# seeker_md_board.net
KiCad netlist of a schematic drawn in EAGLE
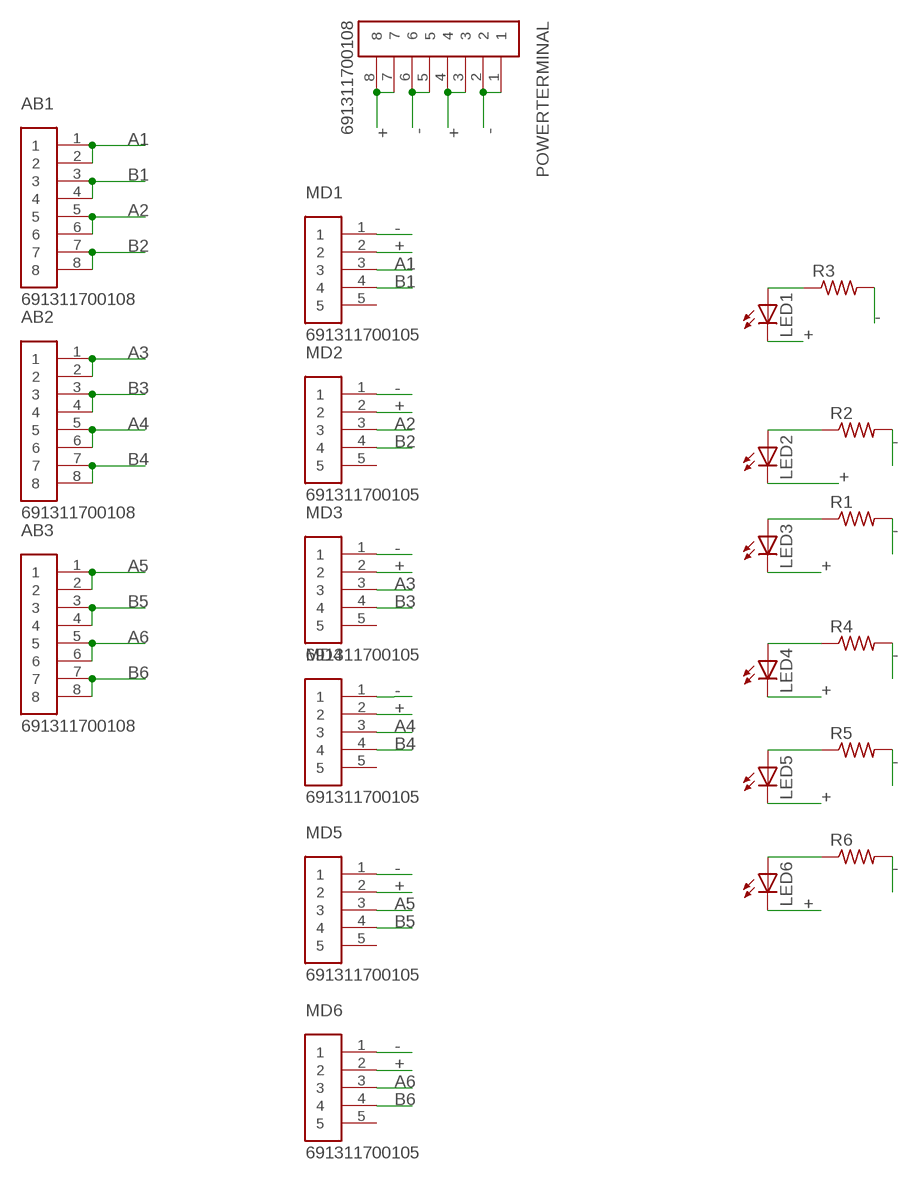
[diagram p0: schematic, sheet 1]

(export (version "E")
  (design (tool "Eeschema 10.0.6"))
  (components
    (comp (ref "AB1")
      (value "691311700108")
      (footprint "eagle-import:TERMINALBLOCK_PLUGGABLE-8-5MM")
      (fields
        (field (name "DIGIKEY_PART_NO") "732-2792-ND")
        (field (name "MANUFACTURER") "WURTH ELEKTRONIK")
        (field (name "CREATED_BY") "PCBLayout.com")
      )
      (libsource (lib "eagle-import") (part "691311700108"))
    )
    (comp (ref "AB2")
      (value "691311700108")
      (footprint "eagle-import:TERMINALBLOCK_PLUGGABLE-8-5MM")
      (fields
        (field (name "DIGIKEY_PART_NO") "732-2792-ND")
        (field (name "MANUFACTURER") "WURTH ELEKTRONIK")
        (field (name "CREATED_BY") "PCBLayout.com")
      )
      (libsource (lib "eagle-import") (part "691311700108"))
    )
    (comp (ref "AB3")
      (value "691311700108")
      (footprint "eagle-import:TERMINALBLOCK_PLUGGABLE-8-5MM")
      (fields
        (field (name "DIGIKEY_PART_NO") "732-2792-ND")
        (field (name "MANUFACTURER") "WURTH ELEKTRONIK")
        (field (name "CREATED_BY") "PCBLayout.com")
      )
      (libsource (lib "eagle-import") (part "691311700108"))
    )
    (comp (ref "LED1")
      (value "LEDLZR181")
      (footprint "eagle-import:LZR181")
      (libsource (lib "eagle-import") (part "LEDLZR181"))
    )
    (comp (ref "LED2")
      (value "LEDLZR181")
      (footprint "eagle-import:LZR181")
      (libsource (lib "eagle-import") (part "LEDLZR181"))
    )
    (comp (ref "LED3")
      (value "LEDLZR181")
      (footprint "eagle-import:LZR181")
      (libsource (lib "eagle-import") (part "LEDLZR181"))
    )
    (comp (ref "LED4")
      (value "LEDLZR181")
      (footprint "eagle-import:LZR181")
      (libsource (lib "eagle-import") (part "LEDLZR181"))
    )
    (comp (ref "LED5")
      (value "LEDLZR181")
      (footprint "eagle-import:LZR181")
      (libsource (lib "eagle-import") (part "LEDLZR181"))
    )
    (comp (ref "LED6")
      (value "LEDLZR181")
      (footprint "eagle-import:LZR181")
      (libsource (lib "eagle-import") (part "LEDLZR181"))
    )
    (comp (ref "MD1")
      (value "691311700105")
      (footprint "eagle-import:TERMINALBLOCK_PLUGGABLE-5-5MM")
      (fields
        (field (name "DIGIKEY_PART_NO") "732-2790-ND")
        (field (name "MANUFACTURER") "WURTH ELEKTRONIK")
        (field (name "CREATED_BY") "PCBLayout.com")
      )
      (libsource (lib "eagle-import") (part "691311700105"))
    )
    (comp (ref "MD2")
      (value "691311700105")
      (footprint "eagle-import:TERMINALBLOCK_PLUGGABLE-5-5MM")
      (fields
        (field (name "DIGIKEY_PART_NO") "732-2790-ND")
        (field (name "MANUFACTURER") "WURTH ELEKTRONIK")
        (field (name "CREATED_BY") "PCBLayout.com")
      )
      (libsource (lib "eagle-import") (part "691311700105"))
    )
    (comp (ref "MD3")
      (value "691311700105")
      (footprint "eagle-import:TERMINALBLOCK_PLUGGABLE-5-5MM")
      (fields
        (field (name "DIGIKEY_PART_NO") "732-2790-ND")
        (field (name "MANUFACTURER") "WURTH ELEKTRONIK")
        (field (name "CREATED_BY") "PCBLayout.com")
      )
      (libsource (lib "eagle-import") (part "691311700105"))
    )
    (comp (ref "MD4")
      (value "691311700105")
      (footprint "eagle-import:TERMINALBLOCK_PLUGGABLE-5-5MM")
      (fields
        (field (name "DIGIKEY_PART_NO") "732-2790-ND")
        (field (name "MANUFACTURER") "WURTH ELEKTRONIK")
        (field (name "CREATED_BY") "PCBLayout.com")
      )
      (libsource (lib "eagle-import") (part "691311700105"))
    )
    (comp (ref "MD5")
      (value "691311700105")
      (footprint "eagle-import:TERMINALBLOCK_PLUGGABLE-5-5MM")
      (fields
        (field (name "DIGIKEY_PART_NO") "732-2790-ND")
        (field (name "MANUFACTURER") "WURTH ELEKTRONIK")
        (field (name "CREATED_BY") "PCBLayout.com")
      )
      (libsource (lib "eagle-import") (part "691311700105"))
    )
    (comp (ref "MD6")
      (value "691311700105")
      (footprint "eagle-import:TERMINALBLOCK_PLUGGABLE-5-5MM")
      (fields
        (field (name "DIGIKEY_PART_NO") "732-2790-ND")
        (field (name "MANUFACTURER") "WURTH ELEKTRONIK")
        (field (name "CREATED_BY") "PCBLayout.com")
      )
      (libsource (lib "eagle-import") (part "691311700105"))
    )
    (comp (ref "POWERTERMINAL")
      (value "691311700108")
      (footprint "eagle-import:TERMINALBLOCK_PLUGGABLE-8-5MM")
      (fields
        (field (name "DIGIKEY_PART_NO") "732-2792-ND")
        (field (name "MANUFACTURER") "WURTH ELEKTRONIK")
        (field (name "CREATED_BY") "PCBLayout.com")
      )
      (libsource (lib "eagle-import") (part "691311700108"))
    )
    (comp (ref "R1")
      (value "R-US_0204/5")
      (footprint "eagle-import:0204_5")
      (libsource (lib "eagle-import") (part "R-US_0204/5"))
    )
    (comp (ref "R2")
      (value "R-US_0204/5")
      (footprint "eagle-import:0204_5")
      (libsource (lib "eagle-import") (part "R-US_0204/5"))
    )
    (comp (ref "R3")
      (value "R-US_0204/5")
      (footprint "eagle-import:0204_5")
      (libsource (lib "eagle-import") (part "R-US_0204/5"))
    )
    (comp (ref "R4")
      (value "R-US_0204/5")
      (footprint "eagle-import:0204_5")
      (libsource (lib "eagle-import") (part "R-US_0204/5"))
    )
    (comp (ref "R5")
      (value "R-US_0204/5")
      (footprint "eagle-import:0204_5")
      (libsource (lib "eagle-import") (part "R-US_0204/5"))
    )
    (comp (ref "R6")
      (value "R-US_0204/5")
      (footprint "eagle-import:0204_5")
      (libsource (lib "eagle-import") (part "R-US_0204/5"))
    )
  )
  (nets
    (net (code "1") (name "/+") (class "Default")
      (node (ref "LED1") (pin "K") (pinfunction "C_K") (pintype "passive"))
      (node (ref "LED2") (pin "K") (pinfunction "C_K") (pintype "passive"))
      (node (ref "LED3") (pin "K") (pinfunction "C_K") (pintype "passive"))
      (node (ref "LED4") (pin "K") (pinfunction "C_K") (pintype "passive"))
      (node (ref "LED5") (pin "K") (pinfunction "C_K") (pintype "passive"))
      (node (ref "LED6") (pin "K") (pinfunction "C_K") (pintype "passive"))
      (node (ref "MD1") (pin "2") (pinfunction "2_2") (pintype "passive"))
      (node (ref "MD2") (pin "2") (pinfunction "2_2") (pintype "passive"))
      (node (ref "MD3") (pin "2") (pinfunction "2_2") (pintype "passive"))
      (node (ref "MD4") (pin "2") (pinfunction "2_2") (pintype "passive"))
      (node (ref "MD5") (pin "2") (pinfunction "2_2") (pintype "passive"))
      (node (ref "MD6") (pin "2") (pinfunction "2_2") (pintype "passive"))
      (node (ref "POWERTERMINAL") (pin "3") (pinfunction "3_3") (pintype "passive"))
      (node (ref "POWERTERMINAL") (pin "4") (pinfunction "4_4") (pintype "passive"))
      (node (ref "POWERTERMINAL") (pin "7") (pinfunction "7_7") (pintype "passive"))
      (node (ref "POWERTERMINAL") (pin "8") (pinfunction "8_8") (pintype "passive"))
    )
    (net (code "2") (name "/-") (class "Default")
      (node (ref "MD1") (pin "1") (pinfunction "1_1") (pintype "passive"))
      (node (ref "MD2") (pin "1") (pinfunction "1_1") (pintype "passive"))
      (node (ref "MD3") (pin "1") (pinfunction "1_1") (pintype "passive"))
      (node (ref "MD4") (pin "1") (pinfunction "1_1") (pintype "passive"))
      (node (ref "MD5") (pin "1") (pinfunction "1_1") (pintype "passive"))
      (node (ref "MD6") (pin "1") (pinfunction "1_1") (pintype "passive"))
      (node (ref "POWERTERMINAL") (pin "1") (pinfunction "1_1") (pintype "passive"))
      (node (ref "POWERTERMINAL") (pin "2") (pinfunction "2_2") (pintype "passive"))
      (node (ref "POWERTERMINAL") (pin "5") (pinfunction "5_5") (pintype "passive"))
      (node (ref "POWERTERMINAL") (pin "6") (pinfunction "6_6") (pintype "passive"))
      (node (ref "R1") (pin "2") (pinfunction "2_2") (pintype "passive"))
      (node (ref "R2") (pin "2") (pinfunction "2_2") (pintype "passive"))
      (node (ref "R3") (pin "2") (pinfunction "2_2") (pintype "passive"))
      (node (ref "R4") (pin "2") (pinfunction "2_2") (pintype "passive"))
      (node (ref "R5") (pin "2") (pinfunction "2_2") (pintype "passive"))
      (node (ref "R6") (pin "2") (pinfunction "2_2") (pintype "passive"))
    )
    (net (code "3") (name "/A1") (class "Default")
      (node (ref "AB1") (pin "1") (pinfunction "1_1") (pintype "passive"))
      (node (ref "AB1") (pin "2") (pinfunction "2_2") (pintype "passive"))
      (node (ref "MD1") (pin "3") (pinfunction "3_3") (pintype "passive"))
    )
    (net (code "4") (name "/A2") (class "Default")
      (node (ref "AB1") (pin "5") (pinfunction "5_5") (pintype "passive"))
      (node (ref "AB1") (pin "6") (pinfunction "6_6") (pintype "passive"))
      (node (ref "MD2") (pin "3") (pinfunction "3_3") (pintype "passive"))
    )
    (net (code "5") (name "/A3") (class "Default")
      (node (ref "AB2") (pin "1") (pinfunction "1_1") (pintype "passive"))
      (node (ref "AB2") (pin "2") (pinfunction "2_2") (pintype "passive"))
      (node (ref "MD3") (pin "3") (pinfunction "3_3") (pintype "passive"))
    )
    (net (code "6") (name "/A4") (class "Default")
      (node (ref "AB2") (pin "5") (pinfunction "5_5") (pintype "passive"))
      (node (ref "AB2") (pin "6") (pinfunction "6_6") (pintype "passive"))
      (node (ref "MD4") (pin "3") (pinfunction "3_3") (pintype "passive"))
    )
    (net (code "7") (name "/A5") (class "Default")
      (node (ref "AB3") (pin "1") (pinfunction "1_1") (pintype "passive"))
      (node (ref "AB3") (pin "2") (pinfunction "2_2") (pintype "passive"))
      (node (ref "MD5") (pin "3") (pinfunction "3_3") (pintype "passive"))
    )
    (net (code "8") (name "/A6") (class "Default")
      (node (ref "AB3") (pin "5") (pinfunction "5_5") (pintype "passive"))
      (node (ref "AB3") (pin "6") (pinfunction "6_6") (pintype "passive"))
      (node (ref "MD6") (pin "3") (pinfunction "3_3") (pintype "passive"))
    )
    (net (code "9") (name "/B1") (class "Default")
      (node (ref "AB1") (pin "3") (pinfunction "3_3") (pintype "passive"))
      (node (ref "AB1") (pin "4") (pinfunction "4_4") (pintype "passive"))
      (node (ref "MD1") (pin "4") (pinfunction "4_4") (pintype "passive"))
    )
    (net (code "10") (name "/B2") (class "Default")
      (node (ref "AB1") (pin "7") (pinfunction "7_7") (pintype "passive"))
      (node (ref "AB1") (pin "8") (pinfunction "8_8") (pintype "passive"))
      (node (ref "MD2") (pin "4") (pinfunction "4_4") (pintype "passive"))
    )
    (net (code "11") (name "/B3") (class "Default")
      (node (ref "AB2") (pin "3") (pinfunction "3_3") (pintype "passive"))
      (node (ref "AB2") (pin "4") (pinfunction "4_4") (pintype "passive"))
      (node (ref "MD3") (pin "4") (pinfunction "4_4") (pintype "passive"))
    )
    (net (code "12") (name "/B4") (class "Default")
      (node (ref "AB2") (pin "7") (pinfunction "7_7") (pintype "passive"))
      (node (ref "AB2") (pin "8") (pinfunction "8_8") (pintype "passive"))
      (node (ref "MD4") (pin "4") (pinfunction "4_4") (pintype "passive"))
    )
    (net (code "13") (name "/B5") (class "Default")
      (node (ref "AB3") (pin "3") (pinfunction "3_3") (pintype "passive"))
      (node (ref "AB3") (pin "4") (pinfunction "4_4") (pintype "passive"))
      (node (ref "MD5") (pin "4") (pinfunction "4_4") (pintype "passive"))
    )
    (net (code "14") (name "/B6") (class "Default")
      (node (ref "AB3") (pin "7") (pinfunction "7_7") (pintype "passive"))
      (node (ref "AB3") (pin "8") (pinfunction "8_8") (pintype "passive"))
      (node (ref "MD6") (pin "4") (pinfunction "4_4") (pintype "passive"))
    )
    (net (code "15") (name "Net-(LED1-PadA)") (class "Default")
      (node (ref "LED1") (pin "A") (pinfunction "A_A") (pintype "passive"))
      (node (ref "R3") (pin "1") (pinfunction "1_1") (pintype "passive"))
    )
    (net (code "16") (name "Net-(LED2-PadA)") (class "Default")
      (node (ref "LED2") (pin "A") (pinfunction "A_A") (pintype "passive"))
      (node (ref "R2") (pin "1") (pinfunction "1_1") (pintype "passive"))
    )
    (net (code "17") (name "Net-(LED3-PadA)") (class "Default")
      (node (ref "LED3") (pin "A") (pinfunction "A_A") (pintype "passive"))
      (node (ref "R1") (pin "1") (pinfunction "1_1") (pintype "passive"))
    )
    (net (code "18") (name "Net-(LED4-PadA)") (class "Default")
      (node (ref "LED4") (pin "A") (pinfunction "A_A") (pintype "passive"))
      (node (ref "R4") (pin "1") (pinfunction "1_1") (pintype "passive"))
    )
    (net (code "19") (name "Net-(LED5-PadA)") (class "Default")
      (node (ref "LED5") (pin "A") (pinfunction "A_A") (pintype "passive"))
      (node (ref "R5") (pin "1") (pinfunction "1_1") (pintype "passive"))
    )
    (net (code "20") (name "Net-(LED6-PadA)") (class "Default")
      (node (ref "LED6") (pin "A") (pinfunction "A_A") (pintype "passive"))
      (node (ref "R6") (pin "1") (pinfunction "1_1") (pintype "passive"))
    )
    (net (code "21") (name "unconnected-(MD1-Pad5)") (class "Default")
      (node (ref "MD1") (pin "5") (pinfunction "5_5") (pintype "passive"))
    )
    (net (code "22") (name "unconnected-(MD2-Pad5)") (class "Default")
      (node (ref "MD2") (pin "5") (pinfunction "5_5") (pintype "passive"))
    )
    (net (code "23") (name "unconnected-(MD3-Pad5)") (class "Default")
      (node (ref "MD3") (pin "5") (pinfunction "5_5") (pintype "passive"))
    )
    (net (code "24") (name "unconnected-(MD4-Pad5)") (class "Default")
      (node (ref "MD4") (pin "5") (pinfunction "5_5") (pintype "passive"))
    )
    (net (code "25") (name "unconnected-(MD5-Pad5)") (class "Default")
      (node (ref "MD5") (pin "5") (pinfunction "5_5") (pintype "passive"))
    )
    (net (code "26") (name "unconnected-(MD6-Pad5)") (class "Default")
      (node (ref "MD6") (pin "5") (pinfunction "5_5") (pintype "passive"))
    )
  )
)
